# LEM_interface.net
KiCad netlist of a schematic drawn in Altium Designer
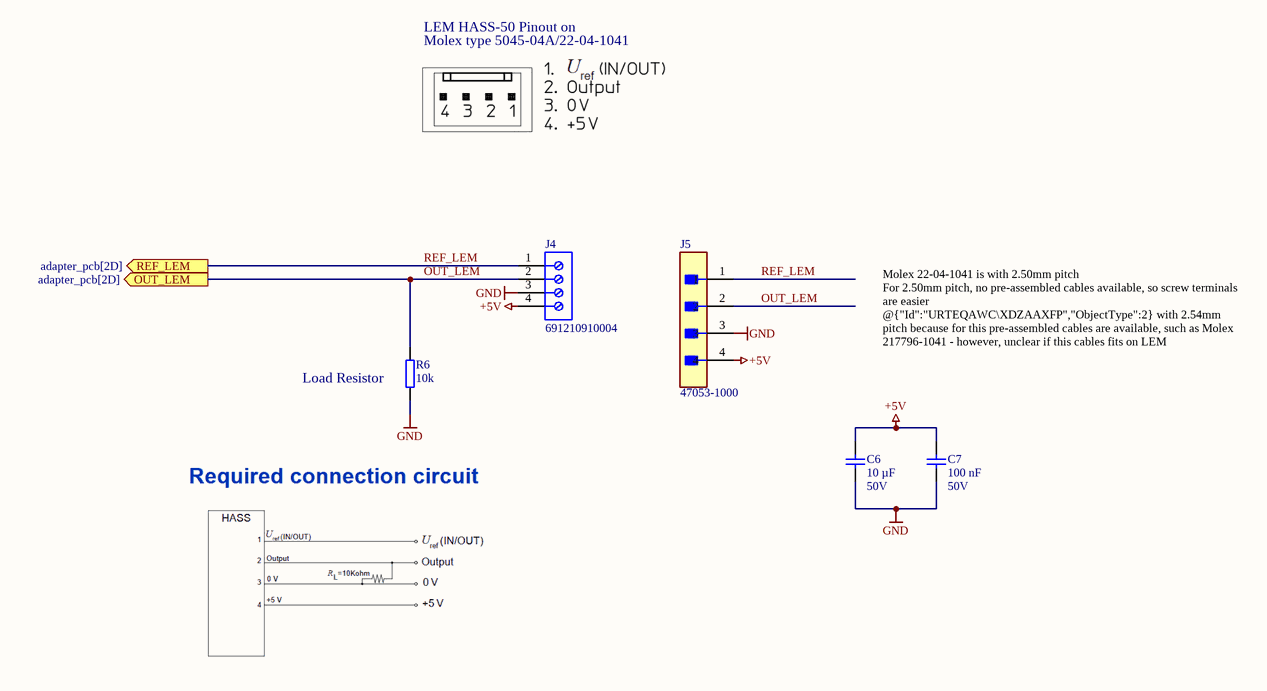
[diagram p0: LEM_interface.SchDoc]

(export (version "E")
  (design (tool "Eeschema 10.0.6"))
  (components
    (comp (ref "C6")
      (value "10 µF")
      (footprint "C_1206_TE")
      (description "Generic capacitor")
      (fields
        (field (name "MANUFACTURER PART NUMBER") "UZgen_C_1206_10uF_50V_X7R")
        (field (name "MANUFACTURER") "UZgen")
        (field (name "VOLTAGE") "50V")
        (field (name "CREATED FROM") "MGeier")
      )
      (libsource (lib "user") (part "CAP-NP"))
    )
    (comp (ref "C7")
      (value "100 nF")
      (footprint "C_0603_TE")
      (description "Generic capacitor")
      (fields
        (field (name "MANUFACTURER PART NUMBER") "UZgen_C_0603_100nF_50V_X7R")
        (field (name "MANUFACTURER") "UZgen")
        (field (name "VOLTAGE") "50V")
        (field (name "CREATED FROM") "AGeiger")
      )
      (libsource (lib "user") (part "CAP-NP"))
    )
    (comp (ref "J4")
      (value "691210910004")
      (footprint "691210910004")
      (description "Tb, Wire To Brd, R/A, 4Way, 18Awg Rohs Compliant: Yes")
      (fields (field (name "LCSC PART NUMBER") "C918122"))
      (libsource (lib "Altium Content Vault") (part "TBL - 1R - 04P - Screw"))
    )
    (comp (ref "J5")
      (value "47053-1000")
      (footprint "FP-470531000-MFG")
      (description "CONN HEADER VERT 4POS 2.54MM")
      (fields (field (name "LCSC PART NUMBER") "C240840"))
      (libsource (lib "Altium Content Vault") (part "299a8cea1bdcbc3624fe62c390fa72c"))
    )
    (comp (ref "R6")
      (value "10k")
      (footprint "R_0603_TE")
      (description "Generic resistor")
      (fields
        (field (name "MANUFACTURER PART NUMBER") "UZgen_R_0603_10k")
        (field (name "MANUFACTURER") "UZgen")
        (field (name "CREATED FROM") "AGeiger")
      )
      (libsource (lib "user") (part "RES"))
    )
  )
  (nets
    (net (code "1") (name "+5V") (class "Default")
      (node (ref "C6") (pin "2") (pinfunction "2_2") (pintype "passive"))
      (node (ref "C7") (pin "2") (pinfunction "2_2") (pintype "passive"))
      (node (ref "J4") (pin "4") (pinfunction "4_4") (pintype "passive"))
      (node (ref "J5") (pin "4") (pinfunction "4_4") (pintype "passive"))
    )
    (net (code "2") (name "/OUT_LEM") (class "Default")
      (node (ref "J4") (pin "2") (pinfunction "2_2") (pintype "passive"))
      (node (ref "J5") (pin "2") (pinfunction "2_2") (pintype "passive"))
      (node (ref "R6") (pin "2") (pinfunction "2_2") (pintype "passive"))
    )
    (net (code "3") (name "/REF_LEM") (class "Default")
      (node (ref "J4") (pin "1") (pinfunction "1_1") (pintype "passive"))
      (node (ref "J5") (pin "1") (pinfunction "1_1") (pintype "passive"))
    )
    (net (code "4") (name "GND") (class "Default")
      (node (ref "C6") (pin "1") (pinfunction "1_1") (pintype "passive"))
      (node (ref "C7") (pin "1") (pinfunction "1_1") (pintype "passive"))
      (node (ref "J4") (pin "3") (pinfunction "3_3") (pintype "passive"))
      (node (ref "J5") (pin "3") (pinfunction "3_3") (pintype "passive"))
      (node (ref "R6") (pin "1") (pinfunction "1_1") (pintype "passive"))
    )
  )
)
